# Sheet1.net
KiCad netlist of a schematic drawn in Altium Designer
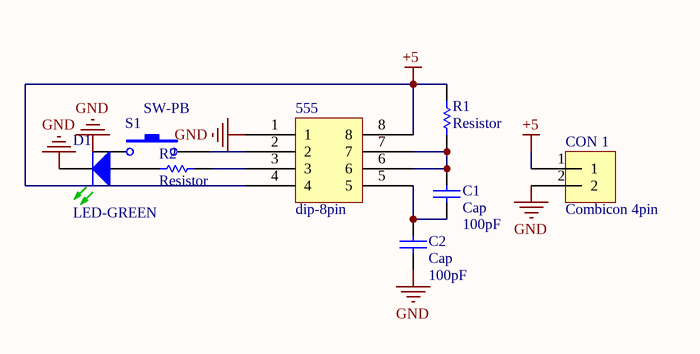
[diagram p0: Sheet1.SchDoc]

(export (version "E")
  (design (tool "Eeschema 10.0.6"))
  (components
    (comp (ref "555")
      (value "dip-8pin")
      (footprint "dip-8pin")
      (libsource (lib "Devindia_v4.0") (part "dip-8pin"))
    )
    (comp (ref "C1")
      (value "Cap")
      (footprint "CAP")
      (description "Capacitor")
      (fields (field (name "ALTIUM_VALUE") "100pF") (field (name "PUBLISHER") "Altium Limited"))
      (libsource (lib "Devindia_v4.0") (part "Cap"))
    )
    (comp (ref "C2")
      (value "Cap")
      (footprint "CAP")
      (description "Capacitor")
      (fields (field (name "ALTIUM_VALUE") "100pF") (field (name "PUBLISHER") "Altium Limited"))
      (libsource (lib "Devindia_v4.0") (part "Cap"))
    )
    (comp (ref "CON 1")
      (value "Combicon 4pin")
      (footprint "combicon-2pin_black")
      (libsource (lib "Devindia_v4.0") (part "Combicon - 2 pin_black"))
    )
    (comp (ref "D1")
      (value "LED-GREEN")
      (footprint "LED-GREEN")
      (description "Typical RED GaAs LED")
      (fields (field (name "PUBLISHER") "Altium Limited"))
      (libsource (lib "Devindia_v2.0") (part "LED-GREEN"))
    )
    (comp (ref "R1")
      (value "Resistor")
      (footprint "res-2.54x4")
      (libsource (lib "Devindia_v4.0") (part "Resistor 2.54x4"))
    )
    (comp (ref "R2")
      (value "Resistor")
      (footprint "res-2.54x5")
      (libsource (lib "Devindia_v2.0") (part "Resistor 2.54x5"))
    )
    (comp (ref "S1")
      (value "SW-PB")
      (footprint "sw-pb")
      (description "Switch")
      (fields (field (name "PUBLISHER") "Altium Limited"))
      (libsource (lib "Devindia_v4.0") (part "SW-PB"))
    )
  )
  (nets
    (net (code "1") (name "+5") (class "Default")
      (node (ref "555") (pin "4") (pinfunction "4_4") (pintype "passive"))
      (node (ref "555") (pin "8") (pinfunction "8_8") (pintype "passive"))
      (node (ref "CON 1") (pin "1") (pinfunction "1_1") (pintype "passive"))
      (node (ref "R1") (pin "2") (pinfunction "2_2") (pintype "passive"))
    )
    (net (code "2") (name "GND") (class "Default")
      (node (ref "555") (pin "1") (pinfunction "1_1") (pintype "passive"))
      (node (ref "C2") (pin "2") (pinfunction "2_2") (pintype "passive"))
      (node (ref "CON 1") (pin "2") (pinfunction "2_2") (pintype "passive"))
      (node (ref "D1") (pin "2") (pinfunction "K_2") (pintype "passive"))
      (node (ref "S1") (pin "1") (pinfunction "1_1") (pintype "passive"))
    )
    (net (code "3") (name "Net-(555-Pad2)") (class "Default")
      (node (ref "555") (pin "2") (pinfunction "2_2") (pintype "passive"))
      (node (ref "S1") (pin "2") (pinfunction "2_2") (pintype "passive"))
    )
    (net (code "4") (name "Net-(555-Pad3)") (class "Default")
      (node (ref "555") (pin "3") (pinfunction "3_3") (pintype "passive"))
      (node (ref "R2") (pin "2") (pinfunction "2_2") (pintype "passive"))
    )
    (net (code "5") (name "Net-(555-Pad5)") (class "Default")
      (node (ref "555") (pin "5") (pinfunction "5_5") (pintype "passive"))
      (node (ref "C1") (pin "1") (pinfunction "1_1") (pintype "passive"))
      (node (ref "C2") (pin "1") (pinfunction "1_1") (pintype "passive"))
    )
    (net (code "6") (name "Net-(555-Pad6)") (class "Default")
      (node (ref "555") (pin "6") (pinfunction "6_6") (pintype "passive"))
      (node (ref "555") (pin "7") (pinfunction "7_7") (pintype "passive"))
      (node (ref "C1") (pin "2") (pinfunction "2_2") (pintype "passive"))
      (node (ref "R1") (pin "1") (pinfunction "1_1") (pintype "passive"))
    )
    (net (code "7") (name "Net-(D1-A)") (class "Default")
      (node (ref "D1") (pin "1") (pinfunction "A_1") (pintype "passive"))
      (node (ref "R2") (pin "1") (pinfunction "1_1") (pintype "passive"))
    )
  )
)
